# MAPLE_CDH_SCH.net
KiCad netlist of a schematic drawn in Altium Designer
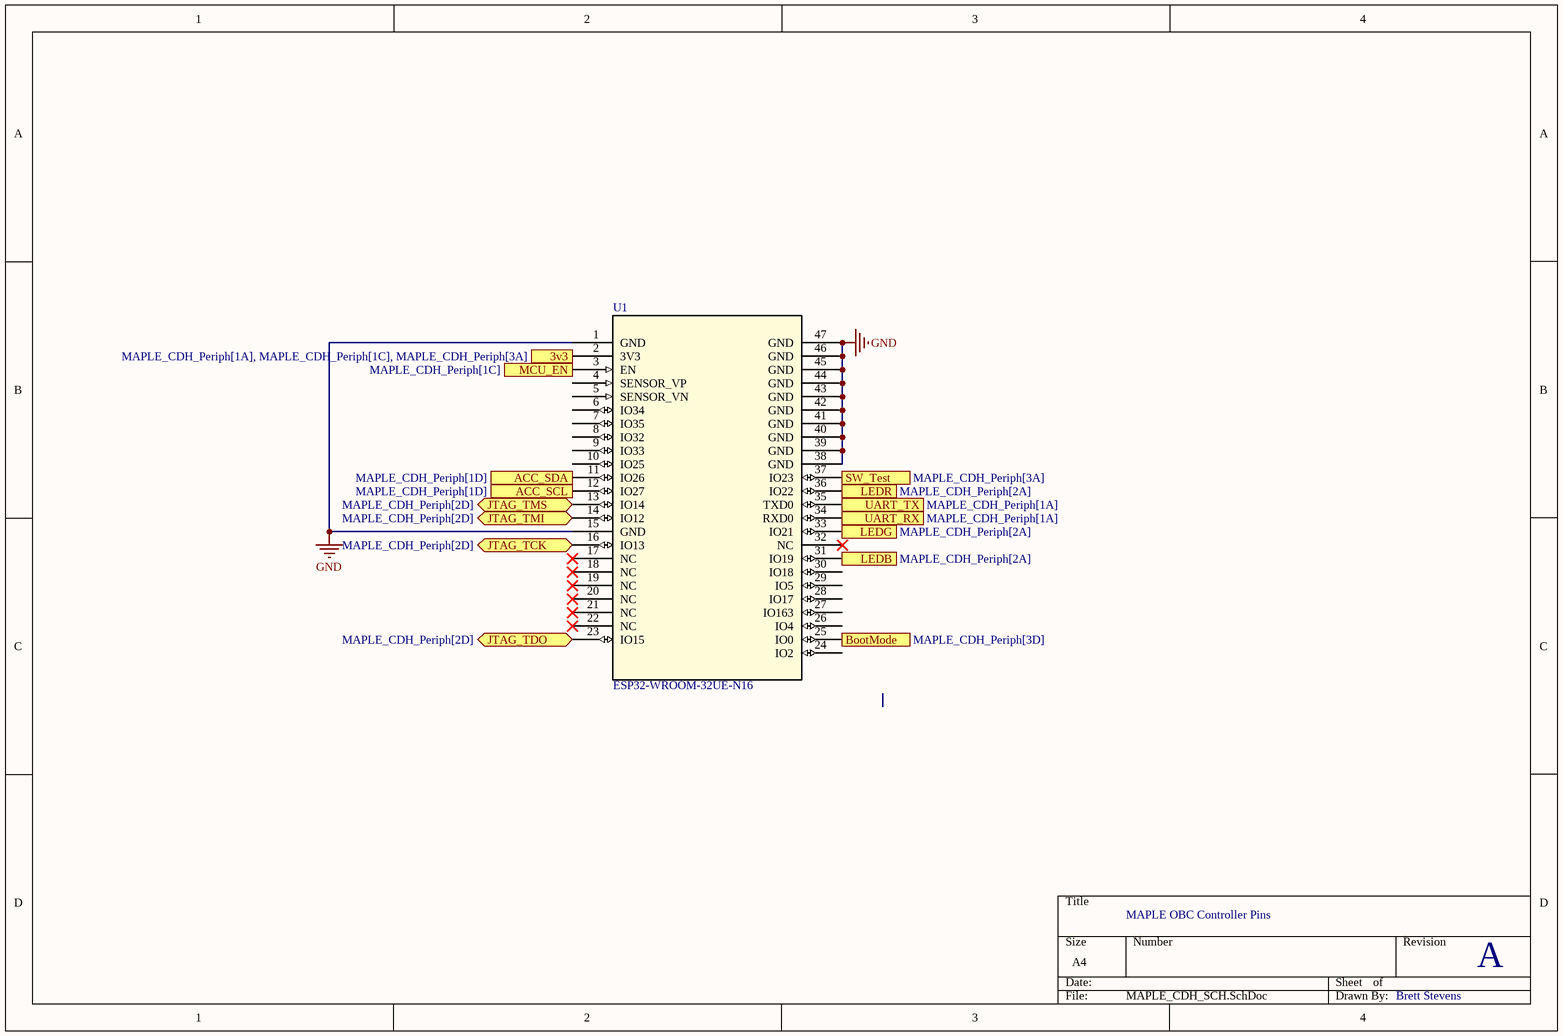
[diagram p0: MAPLE_CDH_SCH.SchDoc]

(export (version "E")
  (design (tool "Eeschema 10.0.6"))
  (components
    (comp (ref "U1")
      (value "ESP32-WROOM-32UE-N16")
      (footprint "ESP32-32UE_EXP")
      (description "No Description Available")
      (fields (field (name "COPYRIGHT") "Copyright (C) 2023 Ultra Librarian. All rights reserved."))
      (libsource (lib "ESP32-WROOM-32UE-N16") (part "ESP32-WROOM-32UE-N16"))
    )
  )
  (nets
    (net (code "1") (name "/3v3") (class "Default")
      (node (ref "U1") (pin "2") (pinfunction "3V3_2") (pintype "power_in"))
    )
    (net (code "2") (name "/ACC_SCL") (class "Default")
      (node (ref "U1") (pin "12") (pinfunction "IO27_12") (pintype "bidirectional"))
    )
    (net (code "3") (name "/ACC_SDA") (class "Default")
      (node (ref "U1") (pin "11") (pinfunction "IO26_11") (pintype "bidirectional"))
    )
    (net (code "4") (name "/BootMode") (class "Default")
      (node (ref "U1") (pin "25") (pinfunction "IO0_25") (pintype "bidirectional"))
    )
    (net (code "5") (name "/JTAG_TCK") (class "Default")
      (node (ref "U1") (pin "16") (pinfunction "IO13_16") (pintype "bidirectional"))
    )
    (net (code "6") (name "/JTAG_TDO") (class "Default")
      (node (ref "U1") (pin "23") (pinfunction "IO15_23") (pintype "bidirectional"))
    )
    (net (code "7") (name "/JTAG_TMI") (class "Default")
      (node (ref "U1") (pin "14") (pinfunction "IO12_14") (pintype "bidirectional"))
    )
    (net (code "8") (name "/JTAG_TMS") (class "Default")
      (node (ref "U1") (pin "13") (pinfunction "IO14_13") (pintype "bidirectional"))
    )
    (net (code "9") (name "/LEDB") (class "Default")
      (node (ref "U1") (pin "31") (pinfunction "IO19_31") (pintype "bidirectional"))
    )
    (net (code "10") (name "/LEDG") (class "Default")
      (node (ref "U1") (pin "33") (pinfunction "IO21_33") (pintype "bidirectional"))
    )
    (net (code "11") (name "/LEDR") (class "Default")
      (node (ref "U1") (pin "36") (pinfunction "IO22_36") (pintype "bidirectional"))
    )
    (net (code "12") (name "/MCU_EN") (class "Default")
      (node (ref "U1") (pin "3") (pinfunction "EN_3") (pintype "input"))
    )
    (net (code "13") (name "/SW_Test") (class "Default")
      (node (ref "U1") (pin "37") (pinfunction "IO23_37") (pintype "bidirectional"))
    )
    (net (code "14") (name "/UART_RX") (class "Default")
      (node (ref "U1") (pin "34") (pinfunction "RXD0_34") (pintype "bidirectional"))
    )
    (net (code "15") (name "/UART_TX") (class "Default")
      (node (ref "U1") (pin "35") (pinfunction "TXD0_35") (pintype "bidirectional"))
    )
    (net (code "16") (name "GND") (class "Default")
      (node (ref "U1") (pin "1") (pinfunction "GND_1") (pintype "power_in"))
      (node (ref "U1") (pin "15") (pinfunction "GND_15") (pintype "power_in"))
      (node (ref "U1") (pin "38") (pinfunction "GND_38") (pintype "power_in"))
      (node (ref "U1") (pin "39") (pinfunction "GND_39") (pintype "power_in"))
      (node (ref "U1") (pin "40") (pinfunction "GND_40") (pintype "power_in"))
      (node (ref "U1") (pin "41") (pinfunction "GND_41") (pintype "power_in"))
      (node (ref "U1") (pin "42") (pinfunction "GND_42") (pintype "power_in"))
      (node (ref "U1") (pin "43") (pinfunction "GND_43") (pintype "power_in"))
      (node (ref "U1") (pin "44") (pinfunction "GND_44") (pintype "power_in"))
      (node (ref "U1") (pin "45") (pinfunction "GND_45") (pintype "power_in"))
      (node (ref "U1") (pin "46") (pinfunction "GND_46") (pintype "power_in"))
      (node (ref "U1") (pin "47") (pinfunction "GND_47") (pintype "power_in"))
    )
    (net (code "17") (name "unconnected-(U1-IO2-Pad24)") (class "Default")
      (node (ref "U1") (pin "24") (pinfunction "IO2_24") (pintype "bidirectional"))
    )
    (net (code "18") (name "unconnected-(U1-IO4-Pad26)") (class "Default")
      (node (ref "U1") (pin "26") (pinfunction "IO4_26") (pintype "bidirectional"))
    )
    (net (code "19") (name "unconnected-(U1-IO5-Pad29)") (class "Default")
      (node (ref "U1") (pin "29") (pinfunction "IO5_29") (pintype "bidirectional"))
    )
    (net (code "20") (name "unconnected-(U1-IO17-Pad28)") (class "Default")
      (node (ref "U1") (pin "28") (pinfunction "IO17_28") (pintype "bidirectional"))
    )
    (net (code "21") (name "unconnected-(U1-IO18-Pad30)") (class "Default")
      (node (ref "U1") (pin "30") (pinfunction "IO18_30") (pintype "bidirectional"))
    )
    (net (code "22") (name "unconnected-(U1-IO25-Pad10)") (class "Default")
      (node (ref "U1") (pin "10") (pinfunction "IO25_10") (pintype "bidirectional"))
    )
    (net (code "23") (name "unconnected-(U1-IO32-Pad8)") (class "Default")
      (node (ref "U1") (pin "8") (pinfunction "IO32_8") (pintype "bidirectional"))
    )
    (net (code "24") (name "unconnected-(U1-IO33-Pad9)") (class "Default")
      (node (ref "U1") (pin "9") (pinfunction "IO33_9") (pintype "bidirectional"))
    )
    (net (code "25") (name "unconnected-(U1-IO34-Pad6)") (class "Default")
      (node (ref "U1") (pin "6") (pinfunction "IO34_6") (pintype "bidirectional"))
    )
    (net (code "26") (name "unconnected-(U1-IO35-Pad7)") (class "Default")
      (node (ref "U1") (pin "7") (pinfunction "IO35_7") (pintype "bidirectional"))
    )
    (net (code "27") (name "unconnected-(U1-IO163-Pad27)") (class "Default")
      (node (ref "U1") (pin "27") (pinfunction "IO163_27") (pintype "bidirectional"))
    )
    (net (code "28") (name "unconnected-(U1-NC-Pad17)") (class "Default")
      (node (ref "U1") (pin "17") (pinfunction "NC_17") (pintype "passive+no_connect"))
    )
    (net (code "29") (name "unconnected-(U1-NC-Pad18)") (class "Default")
      (node (ref "U1") (pin "18") (pinfunction "NC_18") (pintype "passive+no_connect"))
    )
    (net (code "30") (name "unconnected-(U1-NC-Pad19)") (class "Default")
      (node (ref "U1") (pin "19") (pinfunction "NC_19") (pintype "passive+no_connect"))
    )
    (net (code "31") (name "unconnected-(U1-NC-Pad20)") (class "Default")
      (node (ref "U1") (pin "20") (pinfunction "NC_20") (pintype "passive+no_connect"))
    )
    (net (code "32") (name "unconnected-(U1-NC-Pad21)") (class "Default")
      (node (ref "U1") (pin "21") (pinfunction "NC_21") (pintype "passive+no_connect"))
    )
    (net (code "33") (name "unconnected-(U1-NC-Pad22)") (class "Default")
      (node (ref "U1") (pin "22") (pinfunction "NC_22") (pintype "passive+no_connect"))
    )
    (net (code "34") (name "unconnected-(U1-NC-Pad32)") (class "Default")
      (node (ref "U1") (pin "32") (pinfunction "NC_32") (pintype "passive+no_connect"))
    )
    (net (code "35") (name "unconnected-(U1-SENSOR_VN-Pad5)") (class "Default")
      (node (ref "U1") (pin "5") (pinfunction "SENSOR_VN_5") (pintype "input"))
    )
    (net (code "36") (name "unconnected-(U1-SENSOR_VP-Pad4)") (class "Default")
      (node (ref "U1") (pin "4") (pinfunction "SENSOR_VP_4") (pintype "input"))
    )
  )
)
